# Anouchka.net
KiCad netlist of a schematic drawn in EAGLE
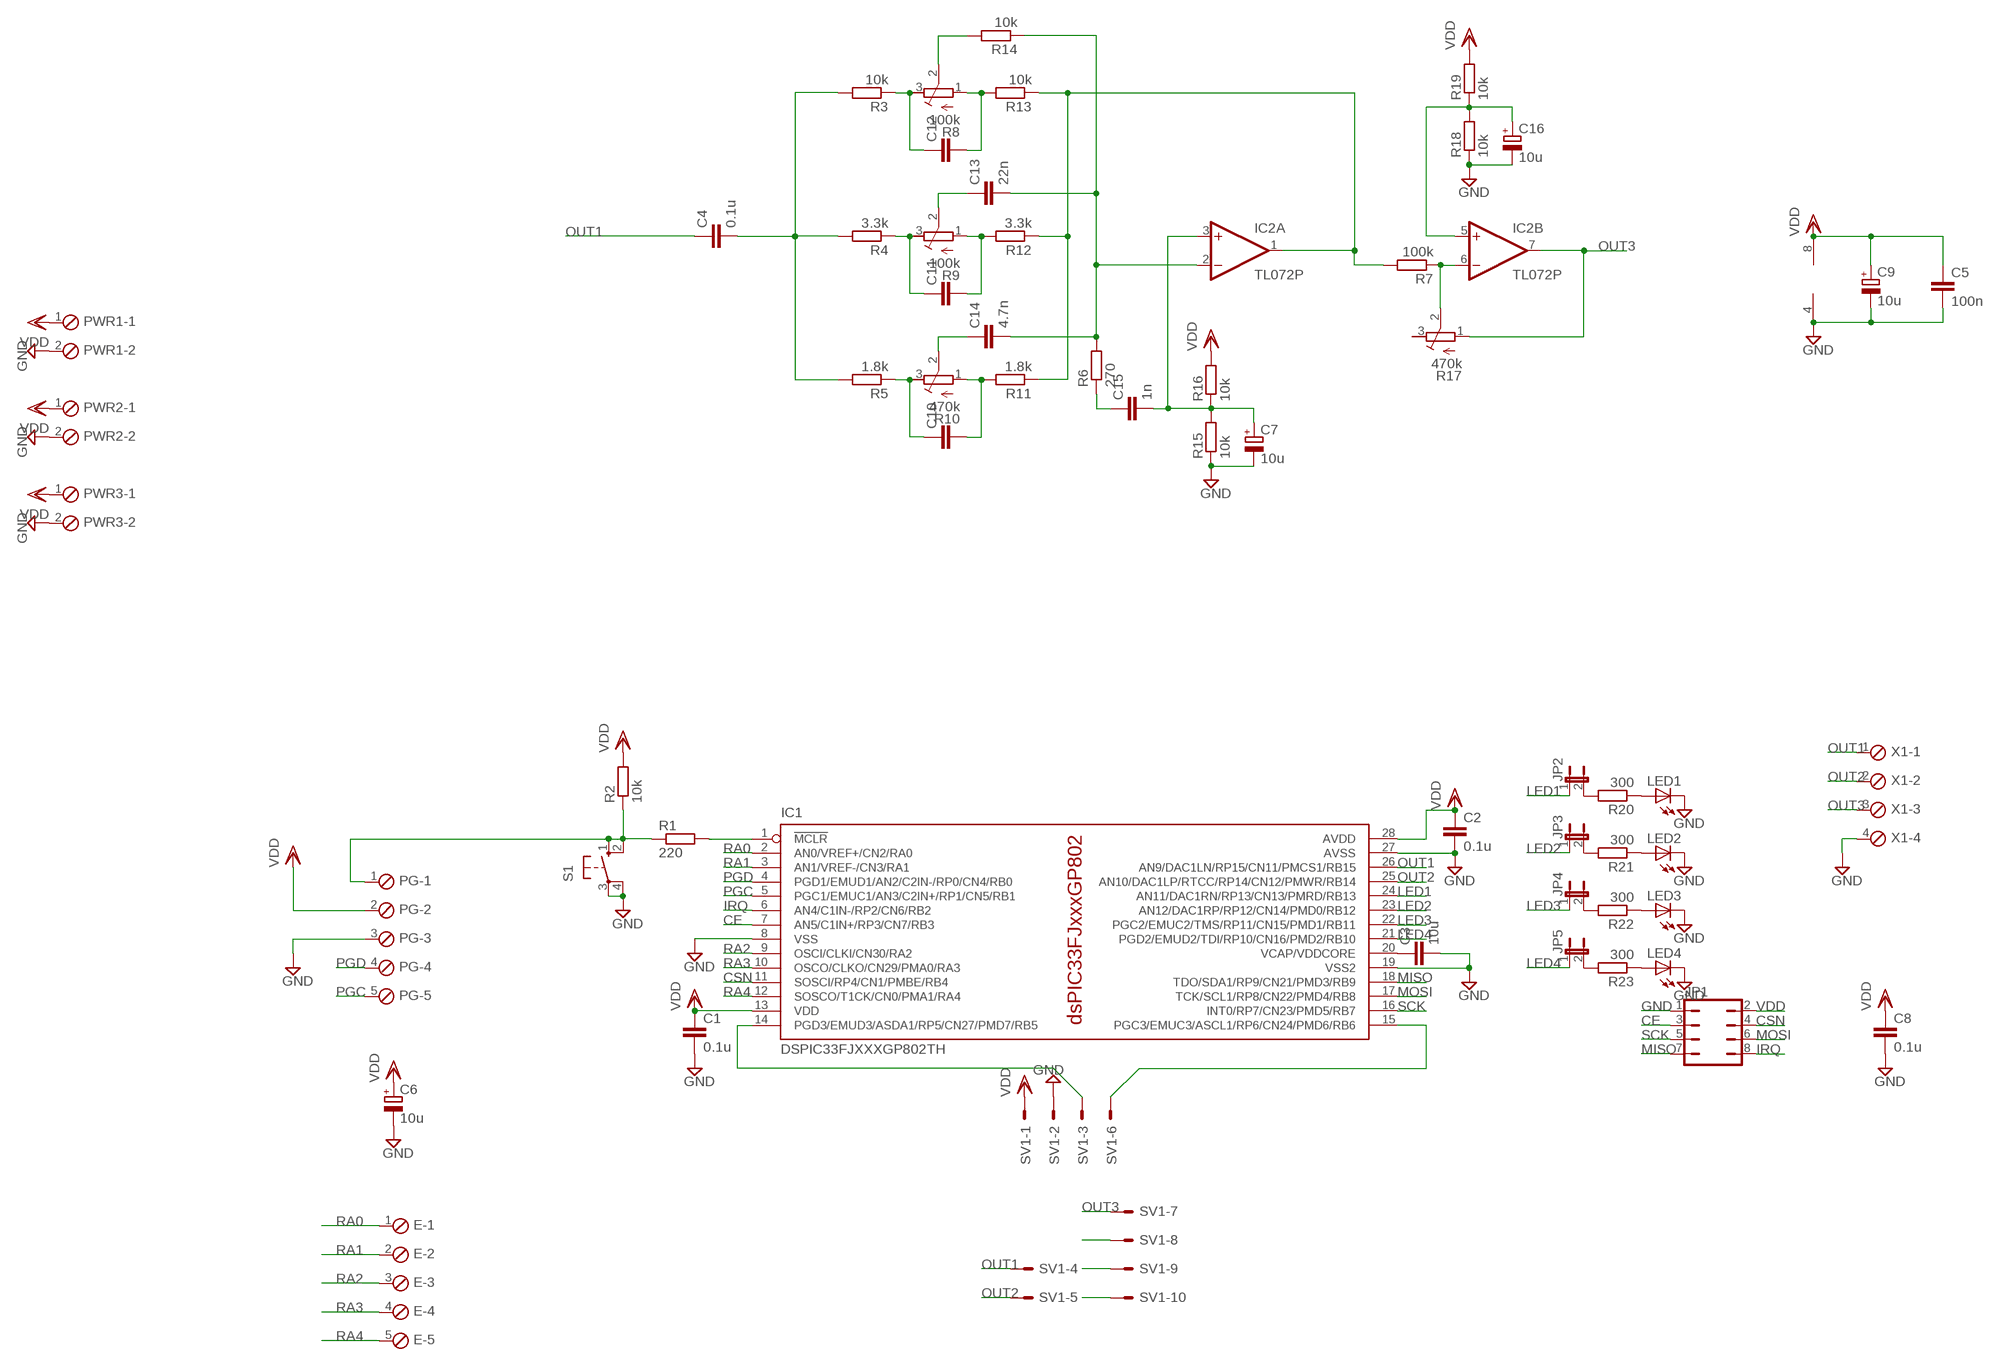
[diagram p0: schematic, sheet 1]

(export (version "E")
  (design (tool "Eeschema 10.0.6"))
  (components
    (comp (ref "C1")
      (value "0.1u")
      (footprint "eagle-import:C025-024X044")
      (libsource (lib "eagle-import") (part "C-EU025-024X044"))
    )
    (comp (ref "C2")
      (value "0.1u")
      (footprint "eagle-import:C025-024X044")
      (libsource (lib "eagle-import") (part "C-EU025-024X044"))
    )
    (comp (ref "C3")
      (value "10u")
      (footprint "eagle-import:C025-024X044")
      (libsource (lib "eagle-import") (part "C-EU025-024X044"))
    )
    (comp (ref "C4")
      (value "0.1u")
      (footprint "eagle-import:C025-024X044")
      (libsource (lib "eagle-import") (part "C-EU025-024X044"))
    )
    (comp (ref "C5")
      (value "100n")
      (footprint "eagle-import:C025-024X044")
      (libsource (lib "eagle-import") (part "C-EU025-024X044"))
    )
    (comp (ref "C6")
      (value "10u")
      (footprint "eagle-import:E2,5-5")
      (libsource (lib "eagle-import") (part "CPOL-EUE2.5-5"))
    )
    (comp (ref "C7")
      (value "10u")
      (footprint "eagle-import:E2,5-5")
      (libsource (lib "eagle-import") (part "CPOL-EUE2.5-5"))
    )
    (comp (ref "C8")
      (value "0.1u")
      (footprint "eagle-import:C025-024X044")
      (libsource (lib "eagle-import") (part "C-EU025-024X044"))
    )
    (comp (ref "C9")
      (value "10u")
      (footprint "eagle-import:E2,5-5")
      (libsource (lib "eagle-import") (part "CPOL-EUE2.5-5"))
    )
    (comp (ref "C10")
      (value "C-EU025-024X044")
      (footprint "eagle-import:C025-024X044")
      (libsource (lib "eagle-import") (part "C-EU025-024X044"))
    )
    (comp (ref "C11")
      (value "C-EU025-024X044")
      (footprint "eagle-import:C025-024X044")
      (libsource (lib "eagle-import") (part "C-EU025-024X044"))
    )
    (comp (ref "C12")
      (value "C-EU025-024X044")
      (footprint "eagle-import:C025-024X044")
      (libsource (lib "eagle-import") (part "C-EU025-024X044"))
    )
    (comp (ref "C13")
      (value "22n")
      (footprint "eagle-import:C025-024X044")
      (libsource (lib "eagle-import") (part "C-EU025-024X044"))
    )
    (comp (ref "C14")
      (value "4.7n")
      (footprint "eagle-import:C025-024X044")
      (libsource (lib "eagle-import") (part "C-EU025-024X044"))
    )
    (comp (ref "C15")
      (value "1n")
      (footprint "eagle-import:C025-024X044")
      (libsource (lib "eagle-import") (part "C-EU025-024X044"))
    )
    (comp (ref "C16")
      (value "10u")
      (footprint "eagle-import:E2,5-5")
      (libsource (lib "eagle-import") (part "CPOL-EUE2.5-5"))
    )
    (comp (ref "E")
      (value "MPT5")
      (footprint "eagle-import:5POL254")
      (libsource (lib "eagle-import") (part "MPT5"))
    )
    (comp (ref "IC1")
      (value "DSPIC33FJXXXGP802TH")
      (footprint "eagle-import:DIL28-3")
      (libsource (lib "eagle-import") (part "DSPIC33FJXXXGP802TH"))
    )
    (comp (ref "IC2")
      (value "TL072P")
      (footprint "eagle-import:DIL08")
      (libsource (lib "eagle-import") (part "TL072P"))
    )
    (comp (ref "JP1")
      (value "JP4Q")
      (footprint "eagle-import:JP4Q")
      (libsource (lib "eagle-import") (part "JP4Q"))
    )
    (comp (ref "JP2")
      (value "JP1E")
      (footprint "eagle-import:JP1")
      (libsource (lib "eagle-import") (part "JP1E"))
    )
    (comp (ref "JP3")
      (value "JP1E")
      (footprint "eagle-import:JP1")
      (libsource (lib "eagle-import") (part "JP1E"))
    )
    (comp (ref "JP4")
      (value "JP1E")
      (footprint "eagle-import:JP1")
      (libsource (lib "eagle-import") (part "JP1E"))
    )
    (comp (ref "JP5")
      (value "JP1E")
      (footprint "eagle-import:JP1")
      (libsource (lib "eagle-import") (part "JP1E"))
    )
    (comp (ref "LED1")
      (value "LED3MM")
      (footprint "eagle-import:LED3MM")
      (libsource (lib "eagle-import") (part "LED3MM"))
    )
    (comp (ref "LED2")
      (value "LED3MM")
      (footprint "eagle-import:LED3MM")
      (libsource (lib "eagle-import") (part "LED3MM"))
    )
    (comp (ref "LED3")
      (value "LED3MM")
      (footprint "eagle-import:LED3MM")
      (libsource (lib "eagle-import") (part "LED3MM"))
    )
    (comp (ref "LED4")
      (value "LED3MM")
      (footprint "eagle-import:LED3MM")
      (libsource (lib "eagle-import") (part "LED3MM"))
    )
    (comp (ref "PG")
      (value "MPT5")
      (footprint "eagle-import:5POL254")
      (libsource (lib "eagle-import") (part "MPT5"))
    )
    (comp (ref "PWR1")
      (value "MPT2")
      (footprint "eagle-import:2POL254")
      (libsource (lib "eagle-import") (part "MPT2"))
    )
    (comp (ref "PWR2")
      (value "MPT2")
      (footprint "eagle-import:2POL254")
      (libsource (lib "eagle-import") (part "MPT2"))
    )
    (comp (ref "PWR3")
      (value "MPT2")
      (footprint "eagle-import:2POL254")
      (libsource (lib "eagle-import") (part "MPT2"))
    )
    (comp (ref "R1")
      (value "220")
      (footprint "eagle-import:0207_10")
      (libsource (lib "eagle-import") (part "R-EU_0207/10"))
    )
    (comp (ref "R2")
      (value "10k")
      (footprint "eagle-import:0207_10")
      (libsource (lib "eagle-import") (part "R-EU_0207/10"))
    )
    (comp (ref "R3")
      (value "10k")
      (footprint "eagle-import:0207_10")
      (libsource (lib "eagle-import") (part "R-EU_0207/10"))
    )
    (comp (ref "R4")
      (value "3.3k")
      (footprint "eagle-import:0207_10")
      (libsource (lib "eagle-import") (part "R-EU_0207/10"))
    )
    (comp (ref "R5")
      (value "1.8k")
      (footprint "eagle-import:0207_10")
      (libsource (lib "eagle-import") (part "R-EU_0207/10"))
    )
    (comp (ref "R6")
      (value "270")
      (footprint "eagle-import:0207_10")
      (libsource (lib "eagle-import") (part "R-EU_0207/10"))
    )
    (comp (ref "R7")
      (value "100k")
      (footprint "eagle-import:0207_10")
      (libsource (lib "eagle-import") (part "R-EU_0207/10"))
    )
    (comp (ref "R8")
      (value "100k")
      (footprint "eagle-import:RTRIM3339P")
      (libsource (lib "eagle-import") (part "R-TRIMM3339P"))
    )
    (comp (ref "R9")
      (value "100k")
      (footprint "eagle-import:RTRIM3339P")
      (libsource (lib "eagle-import") (part "R-TRIMM3339P"))
    )
    (comp (ref "R10")
      (value "470k")
      (footprint "eagle-import:RTRIM3339P")
      (libsource (lib "eagle-import") (part "R-TRIMM3339P"))
    )
    (comp (ref "R11")
      (value "1.8k")
      (footprint "eagle-import:0207_10")
      (libsource (lib "eagle-import") (part "R-EU_0207/10"))
    )
    (comp (ref "R12")
      (value "3.3k")
      (footprint "eagle-import:0207_10")
      (libsource (lib "eagle-import") (part "R-EU_0207/10"))
    )
    (comp (ref "R13")
      (value "10k")
      (footprint "eagle-import:0207_10")
      (libsource (lib "eagle-import") (part "R-EU_0207/10"))
    )
    (comp (ref "R14")
      (value "10k")
      (footprint "eagle-import:0207_10")
      (libsource (lib "eagle-import") (part "R-EU_0207/10"))
    )
    (comp (ref "R15")
      (value "10k")
      (footprint "eagle-import:0207_10")
      (libsource (lib "eagle-import") (part "R-EU_0207/10"))
    )
    (comp (ref "R16")
      (value "10k")
      (footprint "eagle-import:0207_10")
      (libsource (lib "eagle-import") (part "R-EU_0207/10"))
    )
    (comp (ref "R17")
      (value "470k")
      (footprint "eagle-import:RTRIM3339P")
      (libsource (lib "eagle-import") (part "R-TRIMM3339P"))
    )
    (comp (ref "R18")
      (value "10k")
      (footprint "eagle-import:0207_10")
      (libsource (lib "eagle-import") (part "R-EU_0207/10"))
    )
    (comp (ref "R19")
      (value "10k")
      (footprint "eagle-import:0207_10")
      (libsource (lib "eagle-import") (part "R-EU_0207/10"))
    )
    (comp (ref "R20")
      (value "300")
      (footprint "eagle-import:0207_10")
      (libsource (lib "eagle-import") (part "R-EU_0207/10"))
    )
    (comp (ref "R21")
      (value "300")
      (footprint "eagle-import:0207_10")
      (libsource (lib "eagle-import") (part "R-EU_0207/10"))
    )
    (comp (ref "R22")
      (value "300")
      (footprint "eagle-import:0207_10")
      (libsource (lib "eagle-import") (part "R-EU_0207/10"))
    )
    (comp (ref "R23")
      (value "300")
      (footprint "eagle-import:0207_10")
      (libsource (lib "eagle-import") (part "R-EU_0207/10"))
    )
    (comp (ref "S1")
      (value "10-XX")
      (footprint "eagle-import:B3F-10XX")
      (fields (field (name "MPN") "B3F-1000"))
      (libsource (lib "eagle-import") (part "10-XX"))
    )
    (comp (ref "SV1")
      (value "ML10E")
      (footprint "eagle-import:ML10")
      (libsource (lib "eagle-import") (part "ML10E"))
    )
    (comp (ref "X1")
      (value "MPT4")
      (footprint "eagle-import:4POL254")
      (libsource (lib "eagle-import") (part "MPT4"))
    )
  )
  (nets
    (net (code "1") (name "/CE") (class "Default")
      (node (ref "IC1") (pin "7") (pinfunction "AN5/C1IN+/RP3/CN7/RB3_7") (pintype "bidirectional"))
      (node (ref "JP1") (pin "3") (pinfunction "3_3") (pintype "passive"))
    )
    (net (code "2") (name "/CSN") (class "Default")
      (node (ref "IC1") (pin "11") (pinfunction "SOSCI/RP4/CN1/PMBE/RB4_11") (pintype "bidirectional"))
      (node (ref "JP1") (pin "4") (pinfunction "4_4") (pintype "passive"))
    )
    (net (code "3") (name "/IRQ") (class "Default")
      (node (ref "IC1") (pin "6") (pinfunction "AN4/C1IN-/RP2/CN6/RB2_6") (pintype "bidirectional"))
      (node (ref "JP1") (pin "8") (pinfunction "8_8") (pintype "passive"))
    )
    (net (code "4") (name "/LED1") (class "Default")
      (node (ref "IC1") (pin "24") (pinfunction "AN11/DAC1RN/RP13/CN13/PMRD/RB13_24") (pintype "bidirectional"))
      (node (ref "JP2") (pin "1") (pinfunction "1_1") (pintype "passive"))
    )
    (net (code "5") (name "/LED2") (class "Default")
      (node (ref "IC1") (pin "23") (pinfunction "AN12/DAC1RP/RP12/CN14/PMD0/RB12_23") (pintype "bidirectional"))
      (node (ref "JP3") (pin "1") (pinfunction "1_1") (pintype "passive"))
    )
    (net (code "6") (name "/LED3") (class "Default")
      (node (ref "IC1") (pin "22") (pinfunction "PGC2/EMUC2/TMS/RP11/CN15/PMD1/RB11_22") (pintype "bidirectional"))
      (node (ref "JP4") (pin "1") (pinfunction "1_1") (pintype "passive"))
    )
    (net (code "7") (name "/LED4") (class "Default")
      (node (ref "IC1") (pin "21") (pinfunction "PGD2/EMUD2/TDI/RP10/CN16/PMD2/RB10_21") (pintype "bidirectional"))
      (node (ref "JP5") (pin "1") (pinfunction "1_1") (pintype "passive"))
    )
    (net (code "8") (name "/MISO") (class "Default")
      (node (ref "IC1") (pin "18") (pinfunction "TDO/SDA1/RP9/CN21/PMD3/RB9_18") (pintype "bidirectional"))
      (node (ref "JP1") (pin "7") (pinfunction "7_7") (pintype "passive"))
    )
    (net (code "9") (name "/MOSI") (class "Default")
      (node (ref "IC1") (pin "17") (pinfunction "TCK/SCL1/RP8/CN22/PMD4/RB8_17") (pintype "bidirectional"))
      (node (ref "JP1") (pin "6") (pinfunction "6_6") (pintype "passive"))
    )
    (net (code "10") (name "/OUT1") (class "Default")
      (node (ref "C4") (pin "1") (pinfunction "1_1") (pintype "passive"))
      (node (ref "IC1") (pin "26") (pinfunction "AN9/DAC1LN/RP15/CN11/PMCS1/RB15_26") (pintype "bidirectional"))
      (node (ref "SV1") (pin "4") (pinfunction "S_4") (pintype "passive"))
      (node (ref "X1") (pin "1") (pinfunction "1_1") (pintype "passive"))
    )
    (net (code "11") (name "/OUT2") (class "Default")
      (node (ref "IC1") (pin "25") (pinfunction "AN10/DAC1LP/RTCC/RP14/CN12/PMWR/RB14_25") (pintype "bidirectional"))
      (node (ref "SV1") (pin "5") (pinfunction "S_5") (pintype "passive"))
      (node (ref "X1") (pin "2") (pinfunction "1_2") (pintype "passive"))
    )
    (net (code "12") (name "/OUT3") (class "Default")
      (node (ref "IC2") (pin "7") (pinfunction "OUT_7") (pintype "output"))
      (node (ref "R17") (pin "1") (pinfunction "A_1") (pintype "passive"))
      (node (ref "SV1") (pin "7") (pinfunction "S_7") (pintype "passive"))
      (node (ref "X1") (pin "3") (pinfunction "1_3") (pintype "passive"))
    )
    (net (code "13") (name "/PGC") (class "Default")
      (node (ref "IC1") (pin "5") (pinfunction "PGC1/EMUC1/AN3/C2IN+/RP1/CN5/RB1_5") (pintype "bidirectional"))
      (node (ref "PG") (pin "5") (pinfunction "1_5") (pintype "passive"))
    )
    (net (code "14") (name "/PGD") (class "Default")
      (node (ref "IC1") (pin "4") (pinfunction "PGD1/EMUD1/AN2/C2IN-/RP0/CN4/RB0_4") (pintype "bidirectional"))
      (node (ref "PG") (pin "4") (pinfunction "1_4") (pintype "passive"))
    )
    (net (code "15") (name "/RA0") (class "Default")
      (node (ref "E") (pin "1") (pinfunction "1_1") (pintype "passive"))
      (node (ref "IC1") (pin "2") (pinfunction "AN0/VREF+/CN2/RA0_2") (pintype "bidirectional"))
    )
    (net (code "16") (name "/RA1") (class "Default")
      (node (ref "E") (pin "2") (pinfunction "1_2") (pintype "passive"))
      (node (ref "IC1") (pin "3") (pinfunction "AN1/VREF-/CN3/RA1_3") (pintype "bidirectional"))
    )
    (net (code "17") (name "/RA2") (class "Default")
      (node (ref "E") (pin "3") (pinfunction "1_3") (pintype "passive"))
      (node (ref "IC1") (pin "9") (pinfunction "OSCI/CLKI/CN30/RA2_9") (pintype "bidirectional"))
    )
    (net (code "18") (name "/RA3") (class "Default")
      (node (ref "E") (pin "4") (pinfunction "1_4") (pintype "passive"))
      (node (ref "IC1") (pin "10") (pinfunction "OSCO/CLKO/CN29/PMA0/RA3_10") (pintype "bidirectional"))
    )
    (net (code "19") (name "/RA4") (class "Default")
      (node (ref "E") (pin "5") (pinfunction "1_5") (pintype "passive"))
      (node (ref "IC1") (pin "12") (pinfunction "SOSCO/T1CK/CN0/PMA1/RA4_12") (pintype "bidirectional"))
    )
    (net (code "20") (name "/SCK") (class "Default")
      (node (ref "IC1") (pin "16") (pinfunction "INT0/RP7/CN23/PMD5/RB7_16") (pintype "bidirectional"))
      (node (ref "JP1") (pin "5") (pinfunction "5_5") (pintype "passive"))
    )
    (net (code "21") (name "GND") (class "Default")
      (node (ref "C1") (pin "2") (pinfunction "2_2") (pintype "passive"))
      (node (ref "C16") (pin "-") (pinfunction "-_-") (pintype "passive"))
      (node (ref "C2") (pin "2") (pinfunction "2_2") (pintype "passive"))
      (node (ref "C3") (pin "2") (pinfunction "2_2") (pintype "passive"))
      (node (ref "C5") (pin "2") (pinfunction "2_2") (pintype "passive"))
      (node (ref "C6") (pin "-") (pinfunction "-_-") (pintype "passive"))
      (node (ref "C7") (pin "-") (pinfunction "-_-") (pintype "passive"))
      (node (ref "C8") (pin "2") (pinfunction "2_2") (pintype "passive"))
      (node (ref "C9") (pin "-") (pinfunction "-_-") (pintype "passive"))
      (node (ref "IC1") (pin "19") (pinfunction "VSS2_19") (pintype "power_in"))
      (node (ref "IC1") (pin "27") (pinfunction "AVSS_27") (pintype "power_in"))
      (node (ref "IC1") (pin "8") (pinfunction "VSS_8") (pintype "power_in"))
      (node (ref "IC2") (pin "4") (pinfunction "V-_4") (pintype "power_in"))
      (node (ref "JP1") (pin "1") (pinfunction "1_1") (pintype "passive"))
      (node (ref "LED1") (pin "K") (pinfunction "C_K") (pintype "passive"))
      (node (ref "LED2") (pin "K") (pinfunction "C_K") (pintype "passive"))
      (node (ref "LED3") (pin "K") (pinfunction "C_K") (pintype "passive"))
      (node (ref "LED4") (pin "K") (pinfunction "C_K") (pintype "passive"))
      (node (ref "PG") (pin "3") (pinfunction "1_3") (pintype "passive"))
      (node (ref "PWR1") (pin "2") (pinfunction "1_2") (pintype "passive"))
      (node (ref "PWR2") (pin "2") (pinfunction "1_2") (pintype "passive"))
      (node (ref "PWR3") (pin "2") (pinfunction "1_2") (pintype "passive"))
      (node (ref "R15") (pin "1") (pinfunction "1_1") (pintype "passive"))
      (node (ref "R18") (pin "1") (pinfunction "1_1") (pintype "passive"))
      (node (ref "S1") (pin "3") (pinfunction "P_3") (pintype "passive"))
      (node (ref "S1") (pin "4") (pinfunction "P1_4") (pintype "passive"))
      (node (ref "SV1") (pin "2") (pinfunction "S_2") (pintype "passive"))
      (node (ref "X1") (pin "4") (pinfunction "1_4") (pintype "passive"))
    )
    (net (code "22") (name "Net-(C4-Pad2)") (class "Default")
      (node (ref "C4") (pin "2") (pinfunction "2_2") (pintype "passive"))
      (node (ref "R3") (pin "2") (pinfunction "2_2") (pintype "passive"))
      (node (ref "R4") (pin "2") (pinfunction "2_2") (pintype "passive"))
      (node (ref "R5") (pin "2") (pinfunction "2_2") (pintype "passive"))
    )
    (net (code "23") (name "Net-(C15-Pad1)") (class "Default")
      (node (ref "C15") (pin "1") (pinfunction "1_1") (pintype "passive"))
      (node (ref "R6") (pin "1") (pinfunction "1_1") (pintype "passive"))
    )
    (net (code "24") (name "Net-(IC1-PGC3{slash}EMUC3{slash}ASCL1{slash}RP6{slash}CN24{slash}PMD6{slash}RB6)") (class "Default")
      (node (ref "IC1") (pin "15") (pinfunction "PGC3/EMUC3/ASCL1/RP6/CN24/PMD6/RB6_15") (pintype "bidirectional"))
      (node (ref "SV1") (pin "6") (pinfunction "S_6") (pintype "passive"))
    )
    (net (code "25") (name "Net-(IC1-PGD3{slash}EMUD3{slash}ASDA1{slash}RP5{slash}CN27{slash}PMD7{slash}RB5)") (class "Default")
      (node (ref "IC1") (pin "14") (pinfunction "PGD3/EMUD3/ASDA1/RP5/CN27/PMD7/RB5_14") (pintype "bidirectional"))
      (node (ref "SV1") (pin "3") (pinfunction "S_3") (pintype "passive"))
    )
    (net (code "26") (name "Net-(IC1-VCAP{slash}VDDCORE)") (class "Default")
      (node (ref "C3") (pin "1") (pinfunction "1_1") (pintype "passive"))
      (node (ref "IC1") (pin "20") (pinfunction "VCAP/VDDCORE_20") (pintype "power_in"))
    )
    (net (code "27") (name "Net-(IC1-~{MCLR})") (class "Default")
      (node (ref "IC1") (pin "1") (pinfunction "~{MCLR}_1") (pintype "input"))
      (node (ref "R1") (pin "2") (pinfunction "2_2") (pintype "passive"))
    )
    (net (code "28") (name "Net-(IC2A-+IN)") (class "Default")
      (node (ref "C15") (pin "2") (pinfunction "2_2") (pintype "passive"))
      (node (ref "C7") (pin "+") (pinfunction "+_+") (pintype "passive"))
      (node (ref "IC2") (pin "3") (pinfunction "+IN_3") (pintype "input"))
      (node (ref "R15") (pin "2") (pinfunction "2_2") (pintype "passive"))
      (node (ref "R16") (pin "1") (pinfunction "1_1") (pintype "passive"))
    )
    (net (code "29") (name "Net-(IC2A--IN)") (class "Default")
      (node (ref "C13") (pin "2") (pinfunction "2_2") (pintype "passive"))
      (node (ref "C14") (pin "2") (pinfunction "2_2") (pintype "passive"))
      (node (ref "IC2") (pin "2") (pinfunction "-IN_2") (pintype "input"))
      (node (ref "R14") (pin "1") (pinfunction "1_1") (pintype "passive"))
      (node (ref "R6") (pin "2") (pinfunction "2_2") (pintype "passive"))
    )
    (net (code "30") (name "Net-(IC2A-OUT)") (class "Default")
      (node (ref "IC2") (pin "1") (pinfunction "OUT_1") (pintype "output"))
      (node (ref "R11") (pin "1") (pinfunction "1_1") (pintype "passive"))
      (node (ref "R12") (pin "1") (pinfunction "1_1") (pintype "passive"))
      (node (ref "R13") (pin "1") (pinfunction "1_1") (pintype "passive"))
      (node (ref "R7") (pin "2") (pinfunction "2_2") (pintype "passive"))
    )
    (net (code "31") (name "Net-(IC2B-+IN)") (class "Default")
      (node (ref "C16") (pin "+") (pinfunction "+_+") (pintype "passive"))
      (node (ref "IC2") (pin "5") (pinfunction "+IN_5") (pintype "input"))
      (node (ref "R18") (pin "2") (pinfunction "2_2") (pintype "passive"))
      (node (ref "R19") (pin "1") (pinfunction "1_1") (pintype "passive"))
    )
    (net (code "32") (name "Net-(IC2B--IN)") (class "Default")
      (node (ref "IC2") (pin "6") (pinfunction "-IN_6") (pintype "input"))
      (node (ref "R17") (pin "2") (pinfunction "S_2") (pintype "passive"))
      (node (ref "R7") (pin "1") (pinfunction "1_1") (pintype "passive"))
    )
    (net (code "33") (name "Net-(JP2-Pad2)") (class "Default")
      (node (ref "JP2") (pin "2") (pinfunction "2_2") (pintype "passive"))
      (node (ref "R20") (pin "2") (pinfunction "2_2") (pintype "passive"))
    )
    (net (code "34") (name "Net-(JP3-Pad2)") (class "Default")
      (node (ref "JP3") (pin "2") (pinfunction "2_2") (pintype "passive"))
      (node (ref "R21") (pin "2") (pinfunction "2_2") (pintype "passive"))
    )
    (net (code "35") (name "Net-(JP4-Pad2)") (class "Default")
      (node (ref "JP4") (pin "2") (pinfunction "2_2") (pintype "passive"))
      (node (ref "R22") (pin "2") (pinfunction "2_2") (pintype "passive"))
    )
    (net (code "36") (name "Net-(JP5-Pad2)") (class "Default")
      (node (ref "JP5") (pin "2") (pinfunction "2_2") (pintype "passive"))
      (node (ref "R23") (pin "2") (pinfunction "2_2") (pintype "passive"))
    )
    (net (code "37") (name "Net-(LED1-PadA)") (class "Default")
      (node (ref "LED1") (pin "A") (pinfunction "A_A") (pintype "passive"))
      (node (ref "R20") (pin "1") (pinfunction "1_1") (pintype "passive"))
    )
    (net (code "38") (name "Net-(LED2-PadA)") (class "Default")
      (node (ref "LED2") (pin "A") (pinfunction "A_A") (pintype "passive"))
      (node (ref "R21") (pin "1") (pinfunction "1_1") (pintype "passive"))
    )
    (net (code "39") (name "Net-(LED3-PadA)") (class "Default")
      (node (ref "LED3") (pin "A") (pinfunction "A_A") (pintype "passive"))
      (node (ref "R22") (pin "1") (pinfunction "1_1") (pintype "passive"))
    )
    (net (code "40") (name "Net-(LED4-PadA)") (class "Default")
      (node (ref "LED4") (pin "A") (pinfunction "A_A") (pintype "passive"))
      (node (ref "R23") (pin "1") (pinfunction "1_1") (pintype "passive"))
    )
    (net (code "41") (name "Net-(R8-A)") (class "Default")
      (node (ref "C12") (pin "2") (pinfunction "2_2") (pintype "passive"))
      (node (ref "R13") (pin "2") (pinfunction "2_2") (pintype "passive"))
      (node (ref "R8") (pin "1") (pinfunction "A_1") (pintype "passive"))
    )
    (net (code "42") (name "Net-(R8-E)") (class "Default")
      (node (ref "C12") (pin "1") (pinfunction "1_1") (pintype "passive"))
      (node (ref "R3") (pin "1") (pinfunction "1_1") (pintype "passive"))
      (node (ref "R8") (pin "3") (pinfunction "E_3") (pintype "passive"))
    )
    (net (code "43") (name "Net-(R8-S)") (class "Default")
      (node (ref "R14") (pin "2") (pinfunction "2_2") (pintype "passive"))
      (node (ref "R8") (pin "2") (pinfunction "S_2") (pintype "passive"))
    )
    (net (code "44") (name "Net-(R9-A)") (class "Default")
      (node (ref "C11") (pin "2") (pinfunction "2_2") (pintype "passive"))
      (node (ref "R12") (pin "2") (pinfunction "2_2") (pintype "passive"))
      (node (ref "R9") (pin "1") (pinfunction "A_1") (pintype "passive"))
    )
    (net (code "45") (name "Net-(R9-E)") (class "Default")
      (node (ref "C11") (pin "1") (pinfunction "1_1") (pintype "passive"))
      (node (ref "R4") (pin "1") (pinfunction "1_1") (pintype "passive"))
      (node (ref "R9") (pin "3") (pinfunction "E_3") (pintype "passive"))
    )
    (net (code "46") (name "Net-(R9-S)") (class "Default")
      (node (ref "C13") (pin "1") (pinfunction "1_1") (pintype "passive"))
      (node (ref "R9") (pin "2") (pinfunction "S_2") (pintype "passive"))
    )
    (net (code "47") (name "Net-(R10-A)") (class "Default")
      (node (ref "C10") (pin "2") (pinfunction "2_2") (pintype "passive"))
      (node (ref "R10") (pin "1") (pinfunction "A_1") (pintype "passive"))
      (node (ref "R11") (pin "2") (pinfunction "2_2") (pintype "passive"))
    )
    (net (code "48") (name "Net-(R10-E)") (class "Default")
      (node (ref "C10") (pin "1") (pinfunction "1_1") (pintype "passive"))
      (node (ref "R10") (pin "3") (pinfunction "E_3") (pintype "passive"))
      (node (ref "R5") (pin "1") (pinfunction "1_1") (pintype "passive"))
    )
    (net (code "49") (name "Net-(R10-S)") (class "Default")
      (node (ref "C14") (pin "1") (pinfunction "1_1") (pintype "passive"))
      (node (ref "R10") (pin "2") (pinfunction "S_2") (pintype "passive"))
    )
    (net (code "50") (name "Net-(S1-S)") (class "Default")
      (node (ref "PG") (pin "1") (pinfunction "1_1") (pintype "passive"))
      (node (ref "R1") (pin "1") (pinfunction "1_1") (pintype "passive"))
      (node (ref "R2") (pin "1") (pinfunction "1_1") (pintype "passive"))
      (node (ref "S1") (pin "1") (pinfunction "S_1") (pintype "passive"))
      (node (ref "S1") (pin "2") (pinfunction "S1_2") (pintype "passive"))
    )
    (net (code "51") (name "VDD") (class "Default")
      (node (ref "C1") (pin "1") (pinfunction "1_1") (pintype "passive"))
      (node (ref "C2") (pin "1") (pinfunction "1_1") (pintype "passive"))
      (node (ref "C5") (pin "1") (pinfunction "1_1") (pintype "passive"))
      (node (ref "C6") (pin "+") (pinfunction "+_+") (pintype "passive"))
      (node (ref "C8") (pin "1") (pinfunction "1_1") (pintype "passive"))
      (node (ref "C9") (pin "+") (pinfunction "+_+") (pintype "passive"))
      (node (ref "IC1") (pin "13") (pinfunction "VDD_13") (pintype "power_in"))
      (node (ref "IC1") (pin "28") (pinfunction "AVDD_28") (pintype "power_in"))
      (node (ref "IC2") (pin "8") (pinfunction "V+_8") (pintype "power_in"))
      (node (ref "JP1") (pin "2") (pinfunction "2_2") (pintype "passive"))
      (node (ref "PG") (pin "2") (pinfunction "1_2") (pintype "passive"))
      (node (ref "PWR1") (pin "1") (pinfunction "1_1") (pintype "passive"))
      (node (ref "PWR2") (pin "1") (pinfunction "1_1") (pintype "passive"))
      (node (ref "PWR3") (pin "1") (pinfunction "1_1") (pintype "passive"))
      (node (ref "R16") (pin "2") (pinfunction "2_2") (pintype "passive"))
      (node (ref "R19") (pin "2") (pinfunction "2_2") (pintype "passive"))
      (node (ref "R2") (pin "2") (pinfunction "2_2") (pintype "passive"))
      (node (ref "SV1") (pin "1") (pinfunction "S_1") (pintype "passive"))
    )
    (net (code "52") (name "unconnected-(R17-E-Pad3)") (class "Default")
      (node (ref "R17") (pin "3") (pinfunction "E_3") (pintype "passive"))
    )
    (net (code "53") (name "unconnected-(SV1B-S-Pad10)") (class "Default")
      (node (ref "SV1") (pin "10") (pinfunction "S_10") (pintype "passive"))
    )
    (net (code "54") (name "unconnected-(SV1I-S-Pad8)") (class "Default")
      (node (ref "SV1") (pin "8") (pinfunction "S_8") (pintype "passive"))
    )
    (net (code "55") (name "unconnected-(SV1J-S-Pad9)") (class "Default")
      (node (ref "SV1") (pin "9") (pinfunction "S_9") (pintype "passive"))
    )
  )
)
